# MotorDriver.net
KiCad netlist of a schematic drawn in Altium Designer
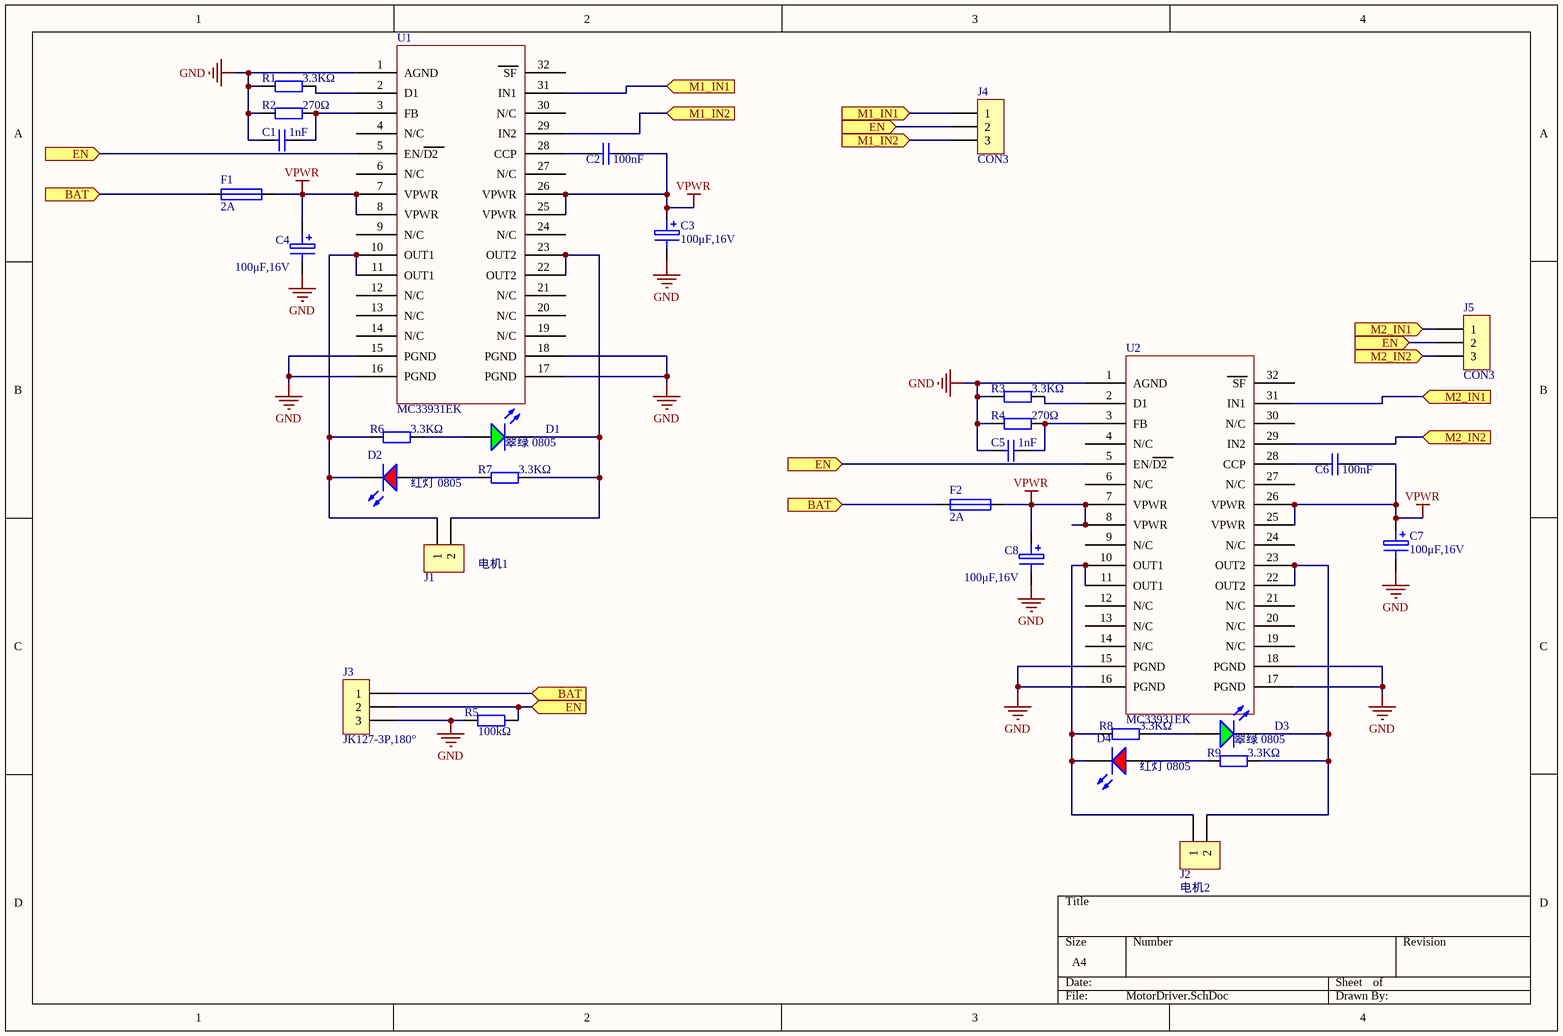
[diagram p0: MotorDriver.SchDoc]

(export (version "E")
  (design (tool "Eeschema 10.0.6"))
  (components
    (comp (ref "C1")
      (value "1nF")
      (footprint "0805_C")
      (description "贴片电容")
      (libsource (lib "Miscellaneous Devices LC") (part "0805 1nF (102) 10% 50V"))
    )
    (comp (ref "C2")
      (value "100nF")
      (footprint "0805_C")
      (description "贴片电容")
      (libsource (lib "Miscellaneous Devices LC") (part "0805 100nF(104) 10% 50V"))
    )
    (comp (ref "C3")
      (value "100μF,16V")
      (footprint "RB-220T")
      (description "Electrolytic Capacitor")
      (libsource (lib "myIntegrated_Library1") (part "CAP ELECTRO1"))
    )
    (comp (ref "C4")
      (value "100μF,16V")
      (footprint "RB-220T")
      (description "Electrolytic Capacitor")
      (libsource (lib "myIntegrated_Library1") (part "CAP ELECTRO1"))
    )
    (comp (ref "C5")
      (value "1nF")
      (footprint "0805_C")
      (description "贴片电容")
      (libsource (lib "Miscellaneous Devices LC") (part "0805 1nF (102) 10% 50V"))
    )
    (comp (ref "C6")
      (value "100nF")
      (footprint "0805_C")
      (description "贴片电容")
      (libsource (lib "Miscellaneous Devices LC") (part "0805 100nF(104) 10% 50V"))
    )
    (comp (ref "C7")
      (value "100μF,16V")
      (footprint "RB-220T")
      (description "Electrolytic Capacitor")
      (libsource (lib "myIntegrated_Library1") (part "CAP ELECTRO1"))
    )
    (comp (ref "C8")
      (value "100μF,16V")
      (footprint "RB-220T")
      (description "Electrolytic Capacitor")
      (libsource (lib "myIntegrated_Library1") (part "CAP ELECTRO1"))
    )
    (comp (ref "D1")
      (value "翠绿 0805")
      (footprint "0805_LED_S1")
      (description "发光二极管")
      (libsource (lib "Miscellaneous Devices LC") (part "0805 翠绿"))
    )
    (comp (ref "D2")
      (value "红灯 0805")
      (footprint "0805_LED_S1")
      (description "发光二极管")
      (libsource (lib "Miscellaneous Devices LC") (part "0805 红灯"))
    )
    (comp (ref "D3")
      (value "翠绿 0805")
      (footprint "0805_LED_S1")
      (description "发光二极管")
      (libsource (lib "Miscellaneous Devices LC") (part "0805 翠绿"))
    )
    (comp (ref "D4")
      (value "红灯 0805")
      (footprint "0805_LED_S1")
      (description "发光二极管")
      (libsource (lib "Miscellaneous Devices LC") (part "0805 红灯"))
    )
    (comp (ref "F1")
      (value "2A")
      (footprint "1812")
      (description "Fuse")
      (libsource (lib "myIntegrated_Library1") (part "FUSE1"))
    )
    (comp (ref "F2")
      (value "2A")
      (footprint "1812")
      (description "Fuse")
      (libsource (lib "myIntegrated_Library1") (part "FUSE1"))
    )
    (comp (ref "J1")
      (value "电机1")
      (footprint "COMZ-2-5.0")
      (description "Connector")
      (fields (field (name "Comment") "CON2"))
      (libsource (lib "myIntegrated_Library1") (part "CON2"))
    )
    (comp (ref "J2")
      (value "电机2")
      (footprint "COMZ-2-5.0")
      (description "Connector")
      (fields (field (name "Comment") "CON2"))
      (libsource (lib "myIntegrated_Library1") (part "CON2"))
    )
    (comp (ref "J3")
      (value "JK127-3P,180°")
      (footprint "COMZ-3-5.0")
      (description "Connector")
      (fields (field (name "Comment") "CON3"))
      (libsource (lib "myIntegrated_Library1") (part "CON3_2"))
    )
    (comp (ref "J4")
      (value "CON3")
      (footprint "SIP-3")
      (description "Connector")
      (libsource (lib "myIntegrated_Library1") (part "CON3_1"))
    )
    (comp (ref "J5")
      (value "CON3")
      (footprint "SIP-3")
      (description "Connector")
      (libsource (lib "myIntegrated_Library1") (part "CON3_1"))
    )
    (comp (ref "R1")
      (value "3.3KΩ")
      (footprint "0805_R")
      (description "贴片电阻")
      (libsource (lib "") (part "0805 3.3KΩ (3301) 1%_1"))
    )
    (comp (ref "R2")
      (value "270Ω")
      (footprint "0805_R")
      (description "贴片电阻")
      (libsource (lib "") (part "0805 3.3KΩ (3301) 1%_1"))
    )
    (comp (ref "R3")
      (value "3.3KΩ")
      (footprint "0805_R")
      (description "贴片电阻")
      (libsource (lib "") (part "0805 3.3KΩ (3301) 1%_1"))
    )
    (comp (ref "R4")
      (value "270Ω")
      (footprint "0805_R")
      (description "贴片电阻")
      (libsource (lib "") (part "0805 3.3KΩ (3301) 1%_1"))
    )
    (comp (ref "R5")
      (value "100kΩ")
      (footprint "0805_R")
      (description "贴片电阻")
      (libsource (lib "Miscellaneous Devices LC") (part "0805 3.3KΩ (3301) 1%"))
    )
    (comp (ref "R6")
      (value "3.3KΩ")
      (footprint "0805_R")
      (description "贴片电阻")
      (libsource (lib "") (part "0805 3.3KΩ (3301) 1%_1"))
    )
    (comp (ref "R7")
      (value "3.3KΩ")
      (footprint "0805_R")
      (description "贴片电阻")
      (libsource (lib "") (part "0805 3.3KΩ (3301) 1%_1"))
    )
    (comp (ref "R8")
      (value "3.3KΩ")
      (footprint "0805_R")
      (description "贴片电阻")
      (libsource (lib "") (part "0805 3.3KΩ (3301) 1%_1"))
    )
    (comp (ref "R9")
      (value "3.3KΩ")
      (footprint "0805_R")
      (description "贴片电阻")
      (libsource (lib "") (part "0805 3.3KΩ (3301) 1%_1"))
    )
    (comp (ref "U1")
      (value "MC33931EK")
      (footprint "MC33931EK_SOP32")
      (libsource (lib "myIntegrated_Library1") (part "MC33931EK"))
    )
    (comp (ref "U2")
      (value "MC33931EK")
      (footprint "MC33931EK_SOP32")
      (libsource (lib "myIntegrated_Library1") (part "MC33931EK"))
    )
  )
  (nets
    (net (code "1") (name "/BAT") (class "Default")
      (node (ref "F1") (pin "1") (pinfunction "1_1") (pintype "passive"))
      (node (ref "F2") (pin "1") (pinfunction "1_1") (pintype "passive"))
      (node (ref "J3") (pin "1") (pinfunction "1_1") (pintype "passive"))
    )
    (net (code "2") (name "/EN") (class "Default")
      (node (ref "J3") (pin "2") (pinfunction "2_2") (pintype "passive"))
      (node (ref "J4") (pin "2") (pinfunction "2_2") (pintype "passive"))
      (node (ref "J5") (pin "2") (pinfunction "2_2") (pintype "passive"))
      (node (ref "R5") (pin "1") (pinfunction "1_1") (pintype "passive"))
      (node (ref "U1") (pin "5") (pinfunction "EN/D2_5") (pintype "passive"))
      (node (ref "U2") (pin "5") (pinfunction "EN/D2_5") (pintype "passive"))
    )
    (net (code "3") (name "/M1_IN1") (class "Default")
      (node (ref "J4") (pin "1") (pinfunction "1_1") (pintype "passive"))
      (node (ref "U1") (pin "31") (pinfunction "IN1_31") (pintype "passive"))
    )
    (net (code "4") (name "/M1_IN2") (class "Default")
      (node (ref "J4") (pin "3") (pinfunction "3_3") (pintype "passive"))
      (node (ref "U1") (pin "29") (pinfunction "IN2_29") (pintype "passive"))
    )
    (net (code "5") (name "/M2_IN1") (class "Default")
      (node (ref "J5") (pin "1") (pinfunction "1_1") (pintype "passive"))
      (node (ref "U2") (pin "31") (pinfunction "IN1_31") (pintype "passive"))
    )
    (net (code "6") (name "/M2_IN2") (class "Default")
      (node (ref "J5") (pin "3") (pinfunction "3_3") (pintype "passive"))
      (node (ref "U2") (pin "29") (pinfunction "IN2_29") (pintype "passive"))
    )
    (net (code "7") (name "GND") (class "Default")
      (node (ref "C1") (pin "1") (pinfunction "1_1") (pintype "passive"))
      (node (ref "C3") (pin "2") (pinfunction "2_2") (pintype "passive"))
      (node (ref "C4") (pin "2") (pinfunction "2_2") (pintype "passive"))
      (node (ref "C5") (pin "1") (pinfunction "1_1") (pintype "passive"))
      (node (ref "C7") (pin "2") (pinfunction "2_2") (pintype "passive"))
      (node (ref "C8") (pin "2") (pinfunction "2_2") (pintype "passive"))
      (node (ref "J3") (pin "3") (pinfunction "3_3") (pintype "passive"))
      (node (ref "R1") (pin "1") (pinfunction "1_1") (pintype "passive"))
      (node (ref "R2") (pin "1") (pinfunction "1_1") (pintype "passive"))
      (node (ref "R3") (pin "1") (pinfunction "1_1") (pintype "passive"))
      (node (ref "R4") (pin "1") (pinfunction "1_1") (pintype "passive"))
      (node (ref "R5") (pin "2") (pinfunction "2_2") (pintype "passive"))
      (node (ref "U1") (pin "1") (pinfunction "AGND_1") (pintype "passive"))
      (node (ref "U1") (pin "15") (pinfunction "PGND_15") (pintype "passive"))
      (node (ref "U1") (pin "16") (pinfunction "PGND_16") (pintype "passive"))
      (node (ref "U1") (pin "17") (pinfunction "PGND_17") (pintype "passive"))
      (node (ref "U1") (pin "18") (pinfunction "PGND_18") (pintype "passive"))
      (node (ref "U2") (pin "1") (pinfunction "AGND_1") (pintype "passive"))
      (node (ref "U2") (pin "15") (pinfunction "PGND_15") (pintype "passive"))
      (node (ref "U2") (pin "16") (pinfunction "PGND_16") (pintype "passive"))
      (node (ref "U2") (pin "17") (pinfunction "PGND_17") (pintype "passive"))
      (node (ref "U2") (pin "18") (pinfunction "PGND_18") (pintype "passive"))
    )
    (net (code "8") (name "Net-(D1-PadA)") (class "Default")
      (node (ref "D1") (pin "A") (pinfunction "A_A") (pintype "passive"))
      (node (ref "R6") (pin "2") (pinfunction "2_2") (pintype "passive"))
    )
    (net (code "9") (name "Net-(D1-PadK)") (class "Default")
      (node (ref "D1") (pin "K") (pinfunction "K_K") (pintype "passive"))
      (node (ref "J1") (pin "2") (pinfunction "2_2") (pintype "passive"))
      (node (ref "R7") (pin "2") (pinfunction "2_2") (pintype "passive"))
      (node (ref "U1") (pin "22") (pinfunction "OUT2_22") (pintype "passive"))
      (node (ref "U1") (pin "23") (pinfunction "OUT2_23") (pintype "passive"))
    )
    (net (code "10") (name "Net-(D2-PadA)") (class "Default")
      (node (ref "D2") (pin "A") (pinfunction "A_A") (pintype "passive"))
      (node (ref "R7") (pin "1") (pinfunction "1_1") (pintype "passive"))
    )
    (net (code "11") (name "Net-(D2-PadK)") (class "Default")
      (node (ref "D2") (pin "K") (pinfunction "K_K") (pintype "passive"))
      (node (ref "J1") (pin "1") (pinfunction "1_1") (pintype "passive"))
      (node (ref "R6") (pin "1") (pinfunction "1_1") (pintype "passive"))
      (node (ref "U1") (pin "10") (pinfunction "OUT1_10") (pintype "passive"))
      (node (ref "U1") (pin "11") (pinfunction "OUT1_11") (pintype "passive"))
    )
    (net (code "12") (name "Net-(D3-PadA)") (class "Default")
      (node (ref "D3") (pin "A") (pinfunction "A_A") (pintype "passive"))
      (node (ref "R8") (pin "2") (pinfunction "2_2") (pintype "passive"))
    )
    (net (code "13") (name "Net-(D3-PadK)") (class "Default")
      (node (ref "D3") (pin "K") (pinfunction "K_K") (pintype "passive"))
      (node (ref "J2") (pin "2") (pinfunction "2_2") (pintype "passive"))
      (node (ref "R9") (pin "2") (pinfunction "2_2") (pintype "passive"))
      (node (ref "U2") (pin "22") (pinfunction "OUT2_22") (pintype "passive"))
      (node (ref "U2") (pin "23") (pinfunction "OUT2_23") (pintype "passive"))
    )
    (net (code "14") (name "Net-(D4-PadA)") (class "Default")
      (node (ref "D4") (pin "A") (pinfunction "A_A") (pintype "passive"))
      (node (ref "R9") (pin "1") (pinfunction "1_1") (pintype "passive"))
    )
    (net (code "15") (name "Net-(D4-PadK)") (class "Default")
      (node (ref "D4") (pin "K") (pinfunction "K_K") (pintype "passive"))
      (node (ref "J2") (pin "1") (pinfunction "1_1") (pintype "passive"))
      (node (ref "R8") (pin "1") (pinfunction "1_1") (pintype "passive"))
      (node (ref "U2") (pin "10") (pinfunction "OUT1_10") (pintype "passive"))
      (node (ref "U2") (pin "11") (pinfunction "OUT1_11") (pintype "passive"))
    )
    (net (code "16") (name "Net-(U1-CCP)") (class "Default")
      (node (ref "C2") (pin "1") (pinfunction "1_1") (pintype "passive"))
      (node (ref "U1") (pin "28") (pinfunction "CCP_28") (pintype "passive"))
    )
    (net (code "17") (name "Net-(U1-D1)") (class "Default")
      (node (ref "R1") (pin "2") (pinfunction "2_2") (pintype "passive"))
      (node (ref "U1") (pin "2") (pinfunction "D1_2") (pintype "passive"))
    )
    (net (code "18") (name "Net-(U1-FB)") (class "Default")
      (node (ref "C1") (pin "2") (pinfunction "2_2") (pintype "passive"))
      (node (ref "R2") (pin "2") (pinfunction "2_2") (pintype "passive"))
      (node (ref "U1") (pin "3") (pinfunction "FB_3") (pintype "passive"))
    )
    (net (code "19") (name "Net-(U2-CCP)") (class "Default")
      (node (ref "C6") (pin "1") (pinfunction "1_1") (pintype "passive"))
      (node (ref "U2") (pin "28") (pinfunction "CCP_28") (pintype "passive"))
    )
    (net (code "20") (name "Net-(U2-D1)") (class "Default")
      (node (ref "R3") (pin "2") (pinfunction "2_2") (pintype "passive"))
      (node (ref "U2") (pin "2") (pinfunction "D1_2") (pintype "passive"))
    )
    (net (code "21") (name "Net-(U2-FB)") (class "Default")
      (node (ref "C5") (pin "2") (pinfunction "2_2") (pintype "passive"))
      (node (ref "R4") (pin "2") (pinfunction "2_2") (pintype "passive"))
      (node (ref "U2") (pin "3") (pinfunction "FB_3") (pintype "passive"))
    )
    (net (code "22") (name "VPWR") (class "Default")
      (node (ref "C2") (pin "2") (pinfunction "2_2") (pintype "passive"))
      (node (ref "C3") (pin "1") (pinfunction "1_1") (pintype "passive"))
      (node (ref "C4") (pin "1") (pinfunction "1_1") (pintype "passive"))
      (node (ref "C6") (pin "2") (pinfunction "2_2") (pintype "passive"))
      (node (ref "C7") (pin "1") (pinfunction "1_1") (pintype "passive"))
      (node (ref "C8") (pin "1") (pinfunction "1_1") (pintype "passive"))
      (node (ref "F1") (pin "2") (pinfunction "2_2") (pintype "passive"))
      (node (ref "F2") (pin "2") (pinfunction "2_2") (pintype "passive"))
      (node (ref "U1") (pin "25") (pinfunction "VPWR_25") (pintype "passive"))
      (node (ref "U1") (pin "26") (pinfunction "VPWR_26") (pintype "passive"))
      (node (ref "U1") (pin "7") (pinfunction "VPWR_7") (pintype "passive"))
      (node (ref "U1") (pin "8") (pinfunction "VPWR_8") (pintype "passive"))
      (node (ref "U2") (pin "25") (pinfunction "VPWR_25") (pintype "passive"))
      (node (ref "U2") (pin "26") (pinfunction "VPWR_26") (pintype "passive"))
      (node (ref "U2") (pin "7") (pinfunction "VPWR_7") (pintype "passive"))
      (node (ref "U2") (pin "8") (pinfunction "VPWR_8") (pintype "passive"))
    )
    (net (code "23") (name "unconnected-(U1-N{slash}C-Pad4)") (class "Default")
      (node (ref "U1") (pin "4") (pinfunction "N/C_4") (pintype "passive"))
    )
    (net (code "24") (name "unconnected-(U1-N{slash}C-Pad6)") (class "Default")
      (node (ref "U1") (pin "6") (pinfunction "N/C_6") (pintype "passive"))
    )
    (net (code "25") (name "unconnected-(U1-N{slash}C-Pad9)") (class "Default")
      (node (ref "U1") (pin "9") (pinfunction "N/C_9") (pintype "passive"))
    )
    (net (code "26") (name "unconnected-(U1-N{slash}C-Pad12)") (class "Default")
      (node (ref "U1") (pin "12") (pinfunction "N/C_12") (pintype "passive"))
    )
    (net (code "27") (name "unconnected-(U1-N{slash}C-Pad13)") (class "Default")
      (node (ref "U1") (pin "13") (pinfunction "N/C_13") (pintype "passive"))
    )
    (net (code "28") (name "unconnected-(U1-N{slash}C-Pad14)") (class "Default")
      (node (ref "U1") (pin "14") (pinfunction "N/C_14") (pintype "passive"))
    )
    (net (code "29") (name "unconnected-(U1-N{slash}C-Pad19)") (class "Default")
      (node (ref "U1") (pin "19") (pinfunction "N/C_19") (pintype "passive"))
    )
    (net (code "30") (name "unconnected-(U1-N{slash}C-Pad20)") (class "Default")
      (node (ref "U1") (pin "20") (pinfunction "N/C_20") (pintype "passive"))
    )
    (net (code "31") (name "unconnected-(U1-N{slash}C-Pad21)") (class "Default")
      (node (ref "U1") (pin "21") (pinfunction "N/C_21") (pintype "passive"))
    )
    (net (code "32") (name "unconnected-(U1-N{slash}C-Pad24)") (class "Default")
      (node (ref "U1") (pin "24") (pinfunction "N/C_24") (pintype "passive"))
    )
    (net (code "33") (name "unconnected-(U1-N{slash}C-Pad27)") (class "Default")
      (node (ref "U1") (pin "27") (pinfunction "N/C_27") (pintype "passive"))
    )
    (net (code "34") (name "unconnected-(U1-N{slash}C-Pad30)") (class "Default")
      (node (ref "U1") (pin "30") (pinfunction "N/C_30") (pintype "passive"))
    )
    (net (code "35") (name "unconnected-(U1-SF-Pad32)") (class "Default")
      (node (ref "U1") (pin "32") (pinfunction "SF_32") (pintype "passive"))
    )
    (net (code "36") (name "unconnected-(U2-N{slash}C-Pad4)") (class "Default")
      (node (ref "U2") (pin "4") (pinfunction "N/C_4") (pintype "passive"))
    )
    (net (code "37") (name "unconnected-(U2-N{slash}C-Pad6)") (class "Default")
      (node (ref "U2") (pin "6") (pinfunction "N/C_6") (pintype "passive"))
    )
    (net (code "38") (name "unconnected-(U2-N{slash}C-Pad9)") (class "Default")
      (node (ref "U2") (pin "9") (pinfunction "N/C_9") (pintype "passive"))
    )
    (net (code "39") (name "unconnected-(U2-N{slash}C-Pad12)") (class "Default")
      (node (ref "U2") (pin "12") (pinfunction "N/C_12") (pintype "passive"))
    )
    (net (code "40") (name "unconnected-(U2-N{slash}C-Pad13)") (class "Default")
      (node (ref "U2") (pin "13") (pinfunction "N/C_13") (pintype "passive"))
    )
    (net (code "41") (name "unconnected-(U2-N{slash}C-Pad14)") (class "Default")
      (node (ref "U2") (pin "14") (pinfunction "N/C_14") (pintype "passive"))
    )
    (net (code "42") (name "unconnected-(U2-N{slash}C-Pad19)") (class "Default")
      (node (ref "U2") (pin "19") (pinfunction "N/C_19") (pintype "passive"))
    )
    (net (code "43") (name "unconnected-(U2-N{slash}C-Pad20)") (class "Default")
      (node (ref "U2") (pin "20") (pinfunction "N/C_20") (pintype "passive"))
    )
    (net (code "44") (name "unconnected-(U2-N{slash}C-Pad21)") (class "Default")
      (node (ref "U2") (pin "21") (pinfunction "N/C_21") (pintype "passive"))
    )
    (net (code "45") (name "unconnected-(U2-N{slash}C-Pad24)") (class "Default")
      (node (ref "U2") (pin "24") (pinfunction "N/C_24") (pintype "passive"))
    )
    (net (code "46") (name "unconnected-(U2-N{slash}C-Pad27)") (class "Default")
      (node (ref "U2") (pin "27") (pinfunction "N/C_27") (pintype "passive"))
    )
    (net (code "47") (name "unconnected-(U2-N{slash}C-Pad30)") (class "Default")
      (node (ref "U2") (pin "30") (pinfunction "N/C_30") (pintype "passive"))
    )
    (net (code "48") (name "unconnected-(U2-SF-Pad32)") (class "Default")
      (node (ref "U2") (pin "32") (pinfunction "SF_32") (pintype "passive"))
    )
  )
)
